# sensorTensao_rev5_1.net
KiCad netlist of a schematic drawn in EAGLE
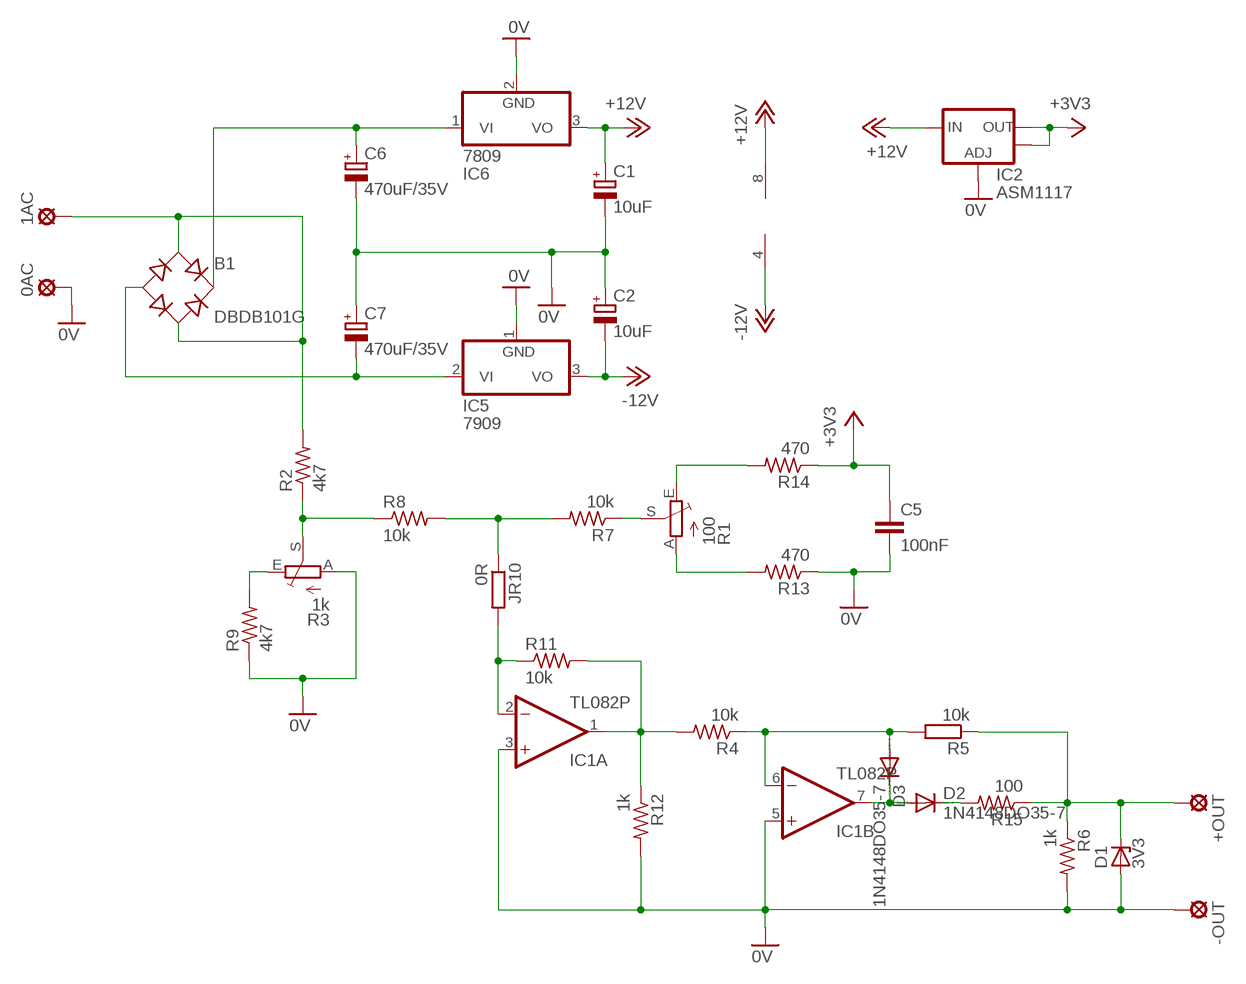
[diagram p0: schematic, sheet 1]

(export (version "E")
  (design (tool "Eeschema 10.0.6"))
  (components
    (comp (ref "+OUT")
      (value "+D")
      (footprint "eagle-import:LSP10")
      (libsource (lib "eagle-import") (part "LSP10"))
    )
    (comp (ref "-OUT")
      (value "0V")
      (footprint "eagle-import:LSP10")
      (libsource (lib "eagle-import") (part "LSP10"))
    )
    (comp (ref "0AC")
      (value "0V")
      (footprint "eagle-import:LSP10")
      (libsource (lib "eagle-import") (part "LSP10"))
    )
    (comp (ref "1AC")
      (value "AC")
      (footprint "eagle-import:LSP10")
      (libsource (lib "eagle-import") (part "LSP10"))
    )
    (comp (ref "B1")
      (value "DBDB101G")
      (footprint "eagle-import:DB")
      (libsource (lib "eagle-import") (part "DB?GDB101"))
    )
    (comp (ref "C1")
      (value "10uF")
      (footprint "eagle-import:E2,5-7")
      (libsource (lib "eagle-import") (part "CPOL-EUE2.5-7"))
    )
    (comp (ref "C2")
      (value "10uF")
      (footprint "eagle-import:E2,5-7")
      (libsource (lib "eagle-import") (part "CPOL-EUE2.5-7"))
    )
    (comp (ref "C5")
      (value "100nF")
      (footprint "eagle-import:C050-024X044")
      (libsource (lib "eagle-import") (part "C-EU050-024X044"))
    )
    (comp (ref "C6")
      (value "470uF/35V")
      (footprint "eagle-import:E3,5-10")
      (libsource (lib "eagle-import") (part "CPOL-EUE3.5-10"))
    )
    (comp (ref "C7")
      (value "470uF/35V")
      (footprint "eagle-import:E3,5-10")
      (libsource (lib "eagle-import") (part "CPOL-EUE3.5-10"))
    )
    (comp (ref "D1")
      (value "3V3")
      (footprint "eagle-import:DO35-7Z")
      (libsource (lib "eagle-import") (part "ZENER-DIODEDO35-7Z"))
    )
    (comp (ref "D2")
      (value "1N4148DO35-7")
      (footprint "eagle-import:DO35-7")
      (libsource (lib "eagle-import") (part "1N4148DO35-7"))
    )
    (comp (ref "D3")
      (value "1N4148DO35-7")
      (footprint "eagle-import:DO35-7")
      (libsource (lib "eagle-import") (part "1N4148DO35-7"))
    )
    (comp (ref "IC1")
      (value "TL082P")
      (footprint "eagle-import:DIL08")
      (libsource (lib "eagle-import") (part "TL082P"))
    )
    (comp (ref "IC2")
      (value "ASM1117")
      (footprint "eagle-import:SOT223")
      (libsource (lib "eagle-import") (part "V_REG_LM1117SOT223"))
    )
    (comp (ref "IC5")
      (value "7909")
      (footprint "eagle-import:TO220V")
      (libsource (lib "eagle-import") (part "7912"))
    )
    (comp (ref "IC6")
      (value "7809")
      (footprint "eagle-import:TO220V")
      (libsource (lib "eagle-import") (part "78TV12"))
    )
    (comp (ref "JR10")
      (value "0R")
      (footprint "eagle-import:0204_12")
      (libsource (lib "eagle-import") (part "R-EU_0204/12"))
    )
    (comp (ref "R1")
      (value "100")
      (footprint "eagle-import:CA6V")
      (libsource (lib "eagle-import") (part "TRIM_EU-CA6V"))
    )
    (comp (ref "R2")
      (value "4k7")
      (footprint "eagle-import:0204_7")
      (libsource (lib "eagle-import") (part "R-US_0204/7"))
    )
    (comp (ref "R3")
      (value "1k")
      (footprint "eagle-import:CA6V")
      (libsource (lib "eagle-import") (part "TRIM_EU-CA6V"))
    )
    (comp (ref "R4")
      (value "10k")
      (footprint "eagle-import:0204_7")
      (libsource (lib "eagle-import") (part "R-US_0204/7"))
    )
    (comp (ref "R5")
      (value "10k")
      (footprint "eagle-import:0204_10")
      (libsource (lib "eagle-import") (part "R-EU_0204/10"))
    )
    (comp (ref "R6")
      (value "1k")
      (footprint "eagle-import:0204_7")
      (libsource (lib "eagle-import") (part "R-US_0204/7"))
    )
    (comp (ref "R7")
      (value "10k")
      (footprint "eagle-import:0204_7")
      (libsource (lib "eagle-import") (part "R-US_0204/7"))
    )
    (comp (ref "R8")
      (value "10k")
      (footprint "eagle-import:0204_7")
      (libsource (lib "eagle-import") (part "R-US_0204/7"))
    )
    (comp (ref "R9")
      (value "4k7")
      (footprint "eagle-import:0204_7")
      (libsource (lib "eagle-import") (part "R-US_0204/7"))
    )
    (comp (ref "R11")
      (value "10k")
      (footprint "eagle-import:0204_7")
      (libsource (lib "eagle-import") (part "R-US_0204/7"))
    )
    (comp (ref "R12")
      (value "1k")
      (footprint "eagle-import:0204_7")
      (libsource (lib "eagle-import") (part "R-US_0204/7"))
    )
    (comp (ref "R13")
      (value "470")
      (footprint "eagle-import:0204_7")
      (libsource (lib "eagle-import") (part "R-US_0204/7"))
    )
    (comp (ref "R14")
      (value "470")
      (footprint "eagle-import:0204_7")
      (libsource (lib "eagle-import") (part "R-US_0204/7"))
    )
    (comp (ref "R15")
      (value "100")
      (footprint "eagle-import:0204_7")
      (libsource (lib "eagle-import") (part "R-US_0204/7"))
    )
  )
  (nets
    (net (code "1") (name "+3V3") (class "Default")
      (node (ref "C5") (pin "1") (pinfunction "1_1") (pintype "passive"))
      (node (ref "IC2") (pin "2") (pinfunction "OUT_2") (pintype "output"))
      (node (ref "IC2") (pin "4") (pinfunction "OUT_4") (pintype "output"))
      (node (ref "R14") (pin "1") (pinfunction "1_1") (pintype "passive"))
    )
    (net (code "2") (name "+12V") (class "Default")
      (node (ref "C1") (pin "+") (pinfunction "+_+") (pintype "passive"))
      (node (ref "IC1") (pin "8") (pinfunction "V+_8") (pintype "power_in"))
      (node (ref "IC2") (pin "3") (pinfunction "IN_3") (pintype "input"))
      (node (ref "IC6") (pin "3") (pinfunction "VO_3") (pintype "passive"))
    )
    (net (code "3") (name "-12V") (class "Default")
      (node (ref "C2") (pin "-") (pinfunction "-_-") (pintype "passive"))
      (node (ref "IC1") (pin "4") (pinfunction "V-_4") (pintype "power_in"))
      (node (ref "IC5") (pin "3") (pinfunction "VO_3") (pintype "passive"))
    )
    (net (code "4") (name "0V") (class "Default")
      (node (ref "-OUT") (pin "MP") (pinfunction "MP_MP") (pintype "passive"))
      (node (ref "0AC") (pin "MP") (pinfunction "MP_MP") (pintype "passive"))
      (node (ref "C1") (pin "-") (pinfunction "-_-") (pintype "passive"))
      (node (ref "C2") (pin "+") (pinfunction "+_+") (pintype "passive"))
      (node (ref "C5") (pin "2") (pinfunction "2_2") (pintype "passive"))
      (node (ref "C6") (pin "-") (pinfunction "-_-") (pintype "passive"))
      (node (ref "C7") (pin "+") (pinfunction "+_+") (pintype "passive"))
      (node (ref "D1") (pin "A") (pinfunction "A_A") (pintype "passive"))
      (node (ref "IC1") (pin "3") (pinfunction "+IN_3") (pintype "input"))
      (node (ref "IC1") (pin "5") (pinfunction "+IN_5") (pintype "input"))
      (node (ref "IC2") (pin "1") (pinfunction "ADJ_1") (pintype "input"))
      (node (ref "IC5") (pin "1") (pinfunction "GND_1") (pintype "passive"))
      (node (ref "IC6") (pin "2") (pinfunction "GND_2") (pintype "passive"))
      (node (ref "R12") (pin "2") (pinfunction "2_2") (pintype "passive"))
      (node (ref "R13") (pin "1") (pinfunction "1_1") (pintype "passive"))
      (node (ref "R3") (pin "A") (pinfunction "A_A") (pintype "passive"))
      (node (ref "R6") (pin "2") (pinfunction "2_2") (pintype "passive"))
      (node (ref "R9") (pin "1") (pinfunction "1_1") (pintype "passive"))
    )
    (net (code "5") (name "Net-(+OUT-PadMP)") (class "Default")
      (node (ref "+OUT") (pin "MP") (pinfunction "MP_MP") (pintype "passive"))
      (node (ref "D1") (pin "C") (pinfunction "C_C") (pintype "passive"))
      (node (ref "R15") (pin "1") (pinfunction "1_1") (pintype "passive"))
      (node (ref "R5") (pin "1") (pinfunction "1_1") (pintype "passive"))
      (node (ref "R6") (pin "1") (pinfunction "1_1") (pintype "passive"))
    )
    (net (code "6") (name "Net-(1AC-PadMP)") (class "Default")
      (node (ref "1AC") (pin "MP") (pinfunction "MP_MP") (pintype "passive"))
      (node (ref "B1") (pin "AC1") (pinfunction "AC1_AC1") (pintype "passive"))
      (node (ref "B1") (pin "AC2") (pinfunction "AC2_AC2") (pintype "passive"))
      (node (ref "R2") (pin "2") (pinfunction "2_2") (pintype "passive"))
    )
    (net (code "7") (name "Net-(D2-PadC)") (class "Default")
      (node (ref "D2") (pin "C") (pinfunction "C_C") (pintype "passive"))
      (node (ref "R15") (pin "2") (pinfunction "2_2") (pintype "passive"))
    )
    (net (code "8") (name "Net-(IC1A--IN)") (class "Default")
      (node (ref "IC1") (pin "2") (pinfunction "-IN_2") (pintype "input"))
      (node (ref "JR10") (pin "2") (pinfunction "2_2") (pintype "passive"))
      (node (ref "R11") (pin "1") (pinfunction "1_1") (pintype "passive"))
    )
    (net (code "9") (name "Net-(IC1A-OUT)") (class "Default")
      (node (ref "IC1") (pin "1") (pinfunction "OUT_1") (pintype "output"))
      (node (ref "R11") (pin "2") (pinfunction "2_2") (pintype "passive"))
      (node (ref "R12") (pin "1") (pinfunction "1_1") (pintype "passive"))
      (node (ref "R4") (pin "2") (pinfunction "2_2") (pintype "passive"))
    )
    (net (code "10") (name "Net-(IC1B--IN)") (class "Default")
      (node (ref "D3") (pin "A") (pinfunction "A_A") (pintype "passive"))
      (node (ref "IC1") (pin "6") (pinfunction "-IN_6") (pintype "input"))
      (node (ref "R4") (pin "1") (pinfunction "1_1") (pintype "passive"))
      (node (ref "R5") (pin "2") (pinfunction "2_2") (pintype "passive"))
    )
    (net (code "11") (name "Net-(IC1B-OUT)") (class "Default")
      (node (ref "D2") (pin "A") (pinfunction "A_A") (pintype "passive"))
      (node (ref "D3") (pin "C") (pinfunction "C_C") (pintype "passive"))
      (node (ref "IC1") (pin "7") (pinfunction "OUT_7") (pintype "output"))
    )
    (net (code "12") (name "Net-(IC5-VI)") (class "Default")
      (node (ref "B1") (pin "-") (pinfunction "-_-") (pintype "passive"))
      (node (ref "C7") (pin "-") (pinfunction "-_-") (pintype "passive"))
      (node (ref "IC5") (pin "2") (pinfunction "VI_2") (pintype "input"))
    )
    (net (code "13") (name "Net-(IC6-VI)") (class "Default")
      (node (ref "B1") (pin "+") (pinfunction "+_+") (pintype "passive"))
      (node (ref "C6") (pin "+") (pinfunction "+_+") (pintype "passive"))
      (node (ref "IC6") (pin "1") (pinfunction "VI_1") (pintype "input"))
    )
    (net (code "14") (name "Net-(JR10-Pad1)") (class "Default")
      (node (ref "JR10") (pin "1") (pinfunction "1_1") (pintype "passive"))
      (node (ref "R7") (pin "2") (pinfunction "2_2") (pintype "passive"))
      (node (ref "R8") (pin "2") (pinfunction "2_2") (pintype "passive"))
    )
    (net (code "15") (name "Net-(R1-PadA)") (class "Default")
      (node (ref "R1") (pin "A") (pinfunction "A_A") (pintype "passive"))
      (node (ref "R13") (pin "2") (pinfunction "2_2") (pintype "passive"))
    )
    (net (code "16") (name "Net-(R1-PadE)") (class "Default")
      (node (ref "R1") (pin "E") (pinfunction "E_E") (pintype "passive"))
      (node (ref "R14") (pin "2") (pinfunction "2_2") (pintype "passive"))
    )
    (net (code "17") (name "Net-(R1-PadS)") (class "Default")
      (node (ref "R1") (pin "S") (pinfunction "S_S") (pintype "passive"))
      (node (ref "R7") (pin "1") (pinfunction "1_1") (pintype "passive"))
    )
    (net (code "18") (name "Net-(R2-Pad1)") (class "Default")
      (node (ref "R2") (pin "1") (pinfunction "1_1") (pintype "passive"))
      (node (ref "R3") (pin "S") (pinfunction "S_S") (pintype "passive"))
      (node (ref "R8") (pin "1") (pinfunction "1_1") (pintype "passive"))
    )
    (net (code "19") (name "Net-(R3-PadE)") (class "Default")
      (node (ref "R3") (pin "E") (pinfunction "E_E") (pintype "passive"))
      (node (ref "R9") (pin "2") (pinfunction "2_2") (pintype "passive"))
    )
  )
)
